# power.net
KiCad netlist of a schematic drawn in Altium Designer
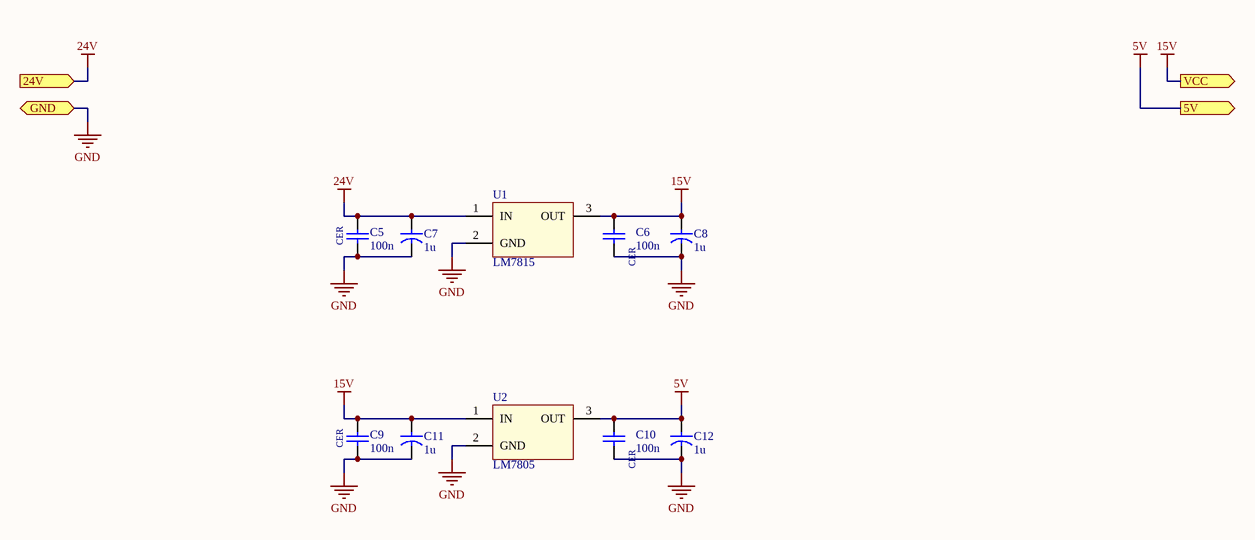
[diagram p0: power.SchDoc]

(export (version "E")
  (design (tool "Eeschema 10.0.6"))
  (components
    (comp (ref "C5") (value "100n") (footprint "CAP_CER_2.50") (libsource (lib "go_kart") (part "CAP_CER")))
    (comp (ref "C6") (value "100n") (footprint "CAP_CER_2.50") (libsource (lib "go_kart") (part "CAP_CER")))
    (comp (ref "C7") (value "1u") (footprint "CAP_ELEC_2.50") (libsource (lib "go_kart") (part "CAP_ELEC")))
    (comp (ref "C8") (value "1u") (footprint "CAP_ELEC_2.50") (libsource (lib "") (part "CAP_ELEC_1")))
    (comp (ref "C9") (value "100n") (footprint "CAP_CER_2.50") (libsource (lib "go_kart") (part "CAP_CER")))
    (comp (ref "C10") (value "100n") (footprint "CAP_CER_2.50") (libsource (lib "go_kart") (part "CAP_CER")))
    (comp (ref "C11") (value "1u") (footprint "CAP_ELEC_2.50") (libsource (lib "go_kart") (part "CAP_ELEC")))
    (comp (ref "C12") (value "1u") (footprint "CAP_ELEC_2.50") (libsource (lib "") (part "CAP_ELEC_1")))
    (comp (ref "U1")
      (value "LM7815")
      (footprint "ONSC-TO-220-3-221A-09")
      (libsource (lib "go_kart") (part "LM7815"))
    )
    (comp (ref "U2")
      (value "LM7805")
      (footprint "ONSC-TO-220-3-221A-09")
      (libsource (lib "go_kart") (part "LM7805"))
    )
  )
  (nets
    (net (code "1") (name "5V") (class "Default")
      (node (ref "C10") (pin "2") (pinfunction "2_2") (pintype "passive"))
      (node (ref "C12") (pin "1") (pinfunction "1_1") (pintype "passive"))
      (node (ref "U2") (pin "3") (pinfunction "OUT_3") (pintype "passive"))
    )
    (net (code "2") (name "15V") (class "Default")
      (node (ref "C11") (pin "1") (pinfunction "1_1") (pintype "passive"))
      (node (ref "C6") (pin "2") (pinfunction "2_2") (pintype "passive"))
      (node (ref "C8") (pin "1") (pinfunction "1_1") (pintype "passive"))
      (node (ref "C9") (pin "2") (pinfunction "2_2") (pintype "passive"))
      (node (ref "U1") (pin "3") (pinfunction "OUT_3") (pintype "passive"))
      (node (ref "U2") (pin "1") (pinfunction "IN_1") (pintype "passive"))
    )
    (net (code "3") (name "24V") (class "Default")
      (node (ref "C5") (pin "2") (pinfunction "2_2") (pintype "passive"))
      (node (ref "C7") (pin "1") (pinfunction "1_1") (pintype "passive"))
      (node (ref "U1") (pin "1") (pinfunction "IN_1") (pintype "passive"))
    )
    (net (code "4") (name "GND") (class "Default")
      (node (ref "C10") (pin "1") (pinfunction "1_1") (pintype "passive"))
      (node (ref "C11") (pin "2") (pinfunction "2_2") (pintype "passive"))
      (node (ref "C12") (pin "2") (pinfunction "2_2") (pintype "passive"))
      (node (ref "C5") (pin "1") (pinfunction "1_1") (pintype "passive"))
      (node (ref "C6") (pin "1") (pinfunction "1_1") (pintype "passive"))
      (node (ref "C7") (pin "2") (pinfunction "2_2") (pintype "passive"))
      (node (ref "C8") (pin "2") (pinfunction "2_2") (pintype "passive"))
      (node (ref "C9") (pin "1") (pinfunction "1_1") (pintype "passive"))
      (node (ref "U1") (pin "2") (pinfunction "GND_2") (pintype "passive"))
      (node (ref "U2") (pin "2") (pinfunction "GND_2") (pintype "passive"))
    )
  )
)
